# 18-USB_HS.net
KiCad netlist of a schematic drawn in Altium Designer
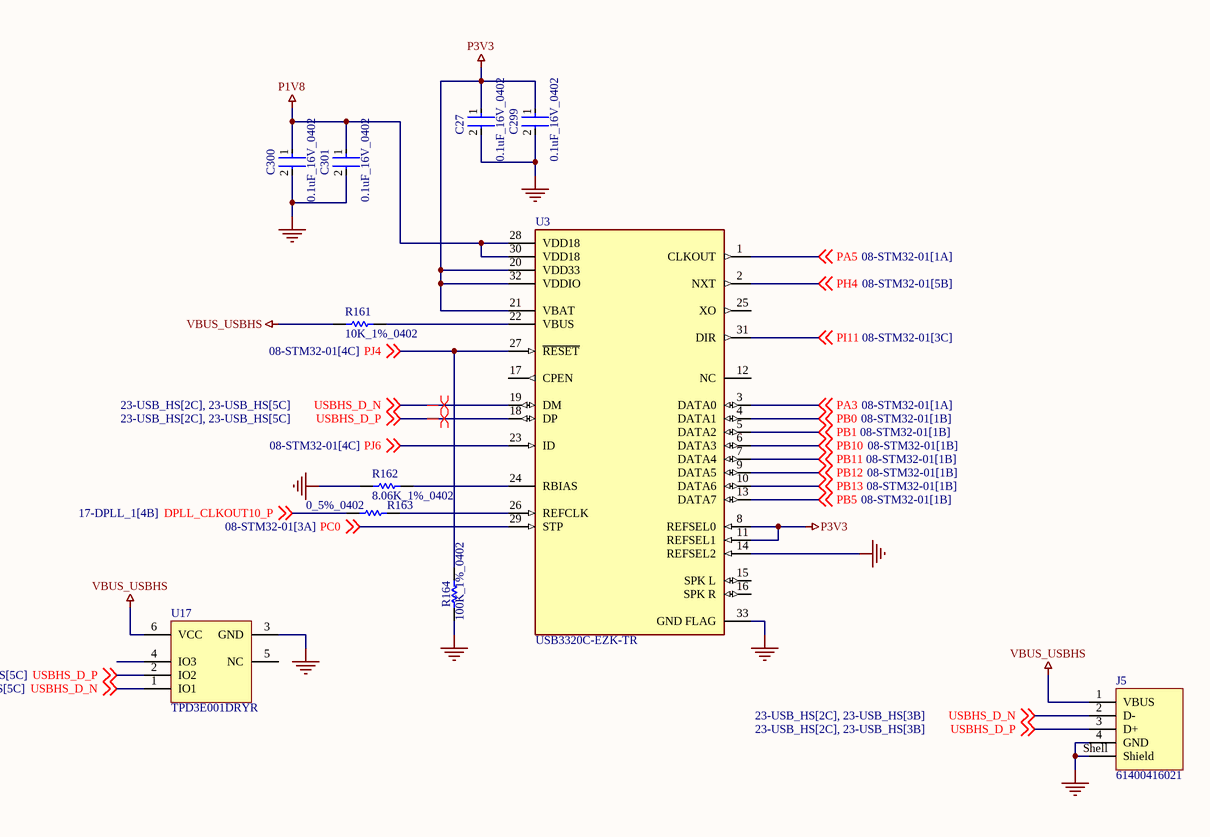
[diagram p0: 18-USB_HS.SchDoc]

(export (version "E")
  (design (tool "Eeschema 10.0.6"))
  (components
    (comp (ref "C27")
      (value "0.1uF_16V_0402")
      (footprint "FP-C0402-BB-MFG")
      (description "CAP CER 0.1UF 16V 5% X7R 0402")
      (fields
        (field (name "MANUFACTURER") "Kemet")
        (field (name "MANUFACTURER PART NUMBER") "C0402C104J4RACTU")
      )
      (libsource (lib "Altium Content Vault") (part "b4654b650e69147ec39a6b967a45e02"))
    )
    (comp (ref "C299")
      (value "0.1uF_16V_0402")
      (footprint "FP-C0402-BB-MFG")
      (description "CAP CER 0.1UF 16V 5% X7R 0402")
      (fields
        (field (name "MANUFACTURER") "Kemet")
        (field (name "MANUFACTURER PART NUMBER") "C0402C104J4RACTU")
      )
      (libsource (lib "Altium Content Vault") (part "b4654b650e69147ec39a6b967a45e02"))
    )
    (comp (ref "C300")
      (value "0.1uF_16V_0402")
      (footprint "FP-C0402-BB-MFG")
      (description "CAP CER 0.1UF 16V 5% X7R 0402")
      (fields
        (field (name "MANUFACTURER") "Kemet")
        (field (name "MANUFACTURER PART NUMBER") "C0402C104J4RACTU")
      )
      (libsource (lib "Altium Content Vault") (part "b4654b650e69147ec39a6b967a45e02"))
    )
    (comp (ref "C301")
      (value "0.1uF_16V_0402")
      (footprint "FP-C0402-BB-MFG")
      (description "CAP CER 0.1UF 16V 5% X7R 0402")
      (fields
        (field (name "MANUFACTURER") "Kemet")
        (field (name "MANUFACTURER PART NUMBER") "C0402C104J4RACTU")
      )
      (libsource (lib "Altium Content Vault") (part "b4654b650e69147ec39a6b967a45e02"))
    )
    (comp (ref "J5")
      (value "61400416021")
      (footprint "61400416021")
      (libsource (lib "Altium Content Vault") (part "USB 2.0_Type A_Receptacle_1 Port"))
    )
    (comp (ref "R161")
      (value "10K_1%_0402")
      (footprint "RESC1005X40X25NL10T10")
      (fields (field (name "MANUFACTURER") "Bourns") (field (name "PART NUMBER") "CR0402-FX-1002GLF"))
      (libsource (lib "Altium Content Vault") (part "RES"))
    )
    (comp (ref "R162")
      (value "8.06K_1%_0402")
      (footprint "RESC1005X40X25LL05T05")
      (fields (field (name "MANUFACTURER") "Panasonic") (field (name "PART NUMBER") "ERJ-2RKF8061X"))
      (libsource (lib "Altium Content Vault") (part "RES"))
    )
    (comp (ref "R163")
      (value "0_5%_0402")
      (footprint "RESC1005X40X25LL10T10")
      (fields (field (name "MANUFACTURER") "KOA Speer") (field (name "PART NUMBER") "RK73Z1ETTP"))
      (libsource (lib "Altium Content Vault") (part "RES"))
    )
    (comp (ref "R164")
      (value "100K_1%_0402")
      (footprint "RESC1005X40X25ML05T10")
      (fields (field (name "MANUFACTURER") "Yageo") (field (name "PART NUMBER") "RC0402FR-13100KL"))
      (libsource (lib "Altium Content Vault") (part "RES"))
    )
    (comp (ref "U3")
      (value "USB3320C-EZK-TR")
      (footprint "FP-32QFN-3304-5X5B-MFG")
      (description "IC TRANSCEIVER HALF 1/1 32QFN")
      (fields
        (field (name "MANUFACTURER") "Microchip")
        (field (name "OCTOPART") "https://octopart.com/usb3320c-ezk-tr-microchip-24995468")
      )
      (libsource (lib "Altium Content Vault") (part "d497a40fedd2315480c30a8e5861190"))
    )
    (comp (ref "U17")
      (value "TPD3E001DRYR")
      (footprint "DRY0006A")
      (fields (field (name "MANUFACTURER") "Texas Instruments"))
      (libsource (lib "Altium Content Vault") (part "TI-TPD3E001-SON_DRY-6"))
    )
  )
  (nets
    (net (code "1") (name "DPLL_CLKOUT10_P") (class "Default")
      (node (ref "R163") (pin "1") (pinfunction "1_1") (pintype "passive"))
    )
    (net (code "2") (name "GND") (class "Default")
      (node (ref "C27") (pin "2") (pinfunction "2_2") (pintype "passive"))
      (node (ref "C299") (pin "2") (pinfunction "2_2") (pintype "passive"))
      (node (ref "C300") (pin "2") (pinfunction "2_2") (pintype "passive"))
      (node (ref "C301") (pin "2") (pinfunction "2_2") (pintype "passive"))
      (node (ref "J5") (pin "4") (pinfunction "GND_4") (pintype "passive"))
      (node (ref "J5") (pin "Shell") (pinfunction "Shield_Shell") (pintype "passive"))
      (node (ref "R162") (pin "1") (pinfunction "1_1") (pintype "passive"))
      (node (ref "R164") (pin "1") (pinfunction "1_1") (pintype "passive"))
      (node (ref "U17") (pin "3") (pinfunction "GND_3") (pintype "power_in"))
      (node (ref "U3") (pin "14") (pinfunction "REFSEL2_14") (pintype "input"))
      (node (ref "U3") (pin "33") (pinfunction "GND_FLAG_33") (pintype "power_in"))
    )
    (net (code "3") (name "Net-(U3-RBIAS)") (class "Default")
      (node (ref "R162") (pin "2") (pinfunction "2_2") (pintype "passive"))
      (node (ref "U3") (pin "24") (pinfunction "RBIAS_24") (pintype "power_in"))
    )
    (net (code "4") (name "Net-(U3-REFCLK)") (class "Default")
      (node (ref "R163") (pin "2") (pinfunction "2_2") (pintype "passive"))
      (node (ref "U3") (pin "26") (pinfunction "REFCLK_26") (pintype "input"))
    )
    (net (code "5") (name "Net-(U3-VBUS)") (class "Default")
      (node (ref "R161") (pin "1") (pinfunction "1_1") (pintype "passive"))
      (node (ref "U3") (pin "22") (pinfunction "VBUS_22") (pintype "power_in"))
    )
    (net (code "6") (name "P1V8") (class "Default")
      (node (ref "C300") (pin "1") (pinfunction "1_1") (pintype "passive"))
      (node (ref "C301") (pin "1") (pinfunction "1_1") (pintype "passive"))
      (node (ref "U3") (pin "28") (pinfunction "VDD18_28") (pintype "power_in"))
      (node (ref "U3") (pin "30") (pinfunction "VDD18_30") (pintype "power_in"))
    )
    (net (code "7") (name "P3V3") (class "Default")
      (node (ref "C27") (pin "1") (pinfunction "1_1") (pintype "passive"))
      (node (ref "C299") (pin "1") (pinfunction "1_1") (pintype "passive"))
      (node (ref "U3") (pin "11") (pinfunction "REFSEL1_11") (pintype "input"))
      (node (ref "U3") (pin "20") (pinfunction "VDD33_20") (pintype "power_in"))
      (node (ref "U3") (pin "21") (pinfunction "VBAT_21") (pintype "power_in"))
      (node (ref "U3") (pin "32") (pinfunction "VDDIO_32") (pintype "power_in"))
      (node (ref "U3") (pin "8") (pinfunction "REFSEL0_8") (pintype "input"))
    )
    (net (code "8") (name "PA3") (class "Default")
      (node (ref "U3") (pin "3") (pinfunction "DATA0_3") (pintype "bidirectional"))
    )
    (net (code "9") (name "PA5") (class "Default")
      (node (ref "U3") (pin "1") (pinfunction "CLKOUT_1") (pintype "output"))
    )
    (net (code "10") (name "PB0") (class "Default")
      (node (ref "U3") (pin "4") (pinfunction "DATA1_4") (pintype "bidirectional"))
    )
    (net (code "11") (name "PB1") (class "Default")
      (node (ref "U3") (pin "5") (pinfunction "DATA2_5") (pintype "bidirectional"))
    )
    (net (code "12") (name "PB5") (class "Default")
      (node (ref "U3") (pin "13") (pinfunction "DATA7_13") (pintype "bidirectional"))
    )
    (net (code "13") (name "PB10") (class "Default")
      (node (ref "U3") (pin "6") (pinfunction "DATA3_6") (pintype "bidirectional"))
    )
    (net (code "14") (name "PB11") (class "Default")
      (node (ref "U3") (pin "7") (pinfunction "DATA4_7") (pintype "bidirectional"))
    )
    (net (code "15") (name "PB12") (class "Default")
      (node (ref "U3") (pin "9") (pinfunction "DATA5_9") (pintype "bidirectional"))
    )
    (net (code "16") (name "PB13") (class "Default")
      (node (ref "U3") (pin "10") (pinfunction "DATA6_10") (pintype "bidirectional"))
    )
    (net (code "17") (name "PC0") (class "Default")
      (node (ref "U3") (pin "29") (pinfunction "STP_29") (pintype "input"))
    )
    (net (code "18") (name "PH4") (class "Default")
      (node (ref "U3") (pin "2") (pinfunction "NXT_2") (pintype "output"))
    )
    (net (code "19") (name "PI11") (class "Default")
      (node (ref "U3") (pin "31") (pinfunction "DIR_31") (pintype "output"))
    )
    (net (code "20") (name "PJ4") (class "Default")
      (node (ref "R164") (pin "2") (pinfunction "2_2") (pintype "passive"))
      (node (ref "U3") (pin "27") (pinfunction "~{RESET}_27") (pintype "input"))
    )
    (net (code "21") (name "PJ6") (class "Default")
      (node (ref "U3") (pin "23") (pinfunction "ID_23") (pintype "input"))
    )
    (net (code "22") (name "USBHS_D_N") (class "Default")
      (node (ref "J5") (pin "2") (pinfunction "D-_2") (pintype "passive"))
      (node (ref "U17") (pin "1") (pinfunction "IO1_1") (pintype "passive"))
      (node (ref "U3") (pin "19") (pinfunction "DM_19") (pintype "bidirectional"))
    )
    (net (code "23") (name "USBHS_D_P") (class "Default")
      (node (ref "J5") (pin "3") (pinfunction "D+_3") (pintype "passive"))
      (node (ref "U17") (pin "2") (pinfunction "IO2_2") (pintype "passive"))
      (node (ref "U3") (pin "18") (pinfunction "DP_18") (pintype "bidirectional"))
    )
    (net (code "24") (name "VBUS_USBHS") (class "Default")
      (node (ref "J5") (pin "1") (pinfunction "VBUS_1") (pintype "passive"))
      (node (ref "R161") (pin "2") (pinfunction "2_2") (pintype "passive"))
      (node (ref "U17") (pin "6") (pinfunction "VCC_6") (pintype "power_in"))
    )
    (net (code "25") (name "unconnected-(U3-CPEN-Pad17)") (class "Default")
      (node (ref "U3") (pin "17") (pinfunction "CPEN_17") (pintype "output"))
    )
    (net (code "26") (name "unconnected-(U3-NC-Pad12)") (class "Default")
      (node (ref "U3") (pin "12") (pinfunction "NC_12") (pintype "passive"))
    )
    (net (code "27") (name "unconnected-(U3-SPK_L-Pad15)") (class "Default")
      (node (ref "U3") (pin "15") (pinfunction "SPK_L_15") (pintype "bidirectional"))
    )
    (net (code "28") (name "unconnected-(U3-SPK_R-Pad16)") (class "Default")
      (node (ref "U3") (pin "16") (pinfunction "SPK_R_16") (pintype "bidirectional"))
    )
    (net (code "29") (name "unconnected-(U3-XO-Pad25)") (class "Default")
      (node (ref "U3") (pin "25") (pinfunction "XO_25") (pintype "output"))
    )
    (net (code "30") (name "unconnected-(U17-IO3-Pad4)") (class "Default")
      (node (ref "U17") (pin "4") (pinfunction "IO3_4") (pintype "passive"))
    )
    (net (code "31") (name "unconnected-(U17-NC-Pad5)") (class "Default")
      (node (ref "U17") (pin "5") (pinfunction "NC_5") (pintype "passive"))
    )
  )
)
